# microcontroller3.net
KiCad netlist of a schematic drawn in Altium Designer
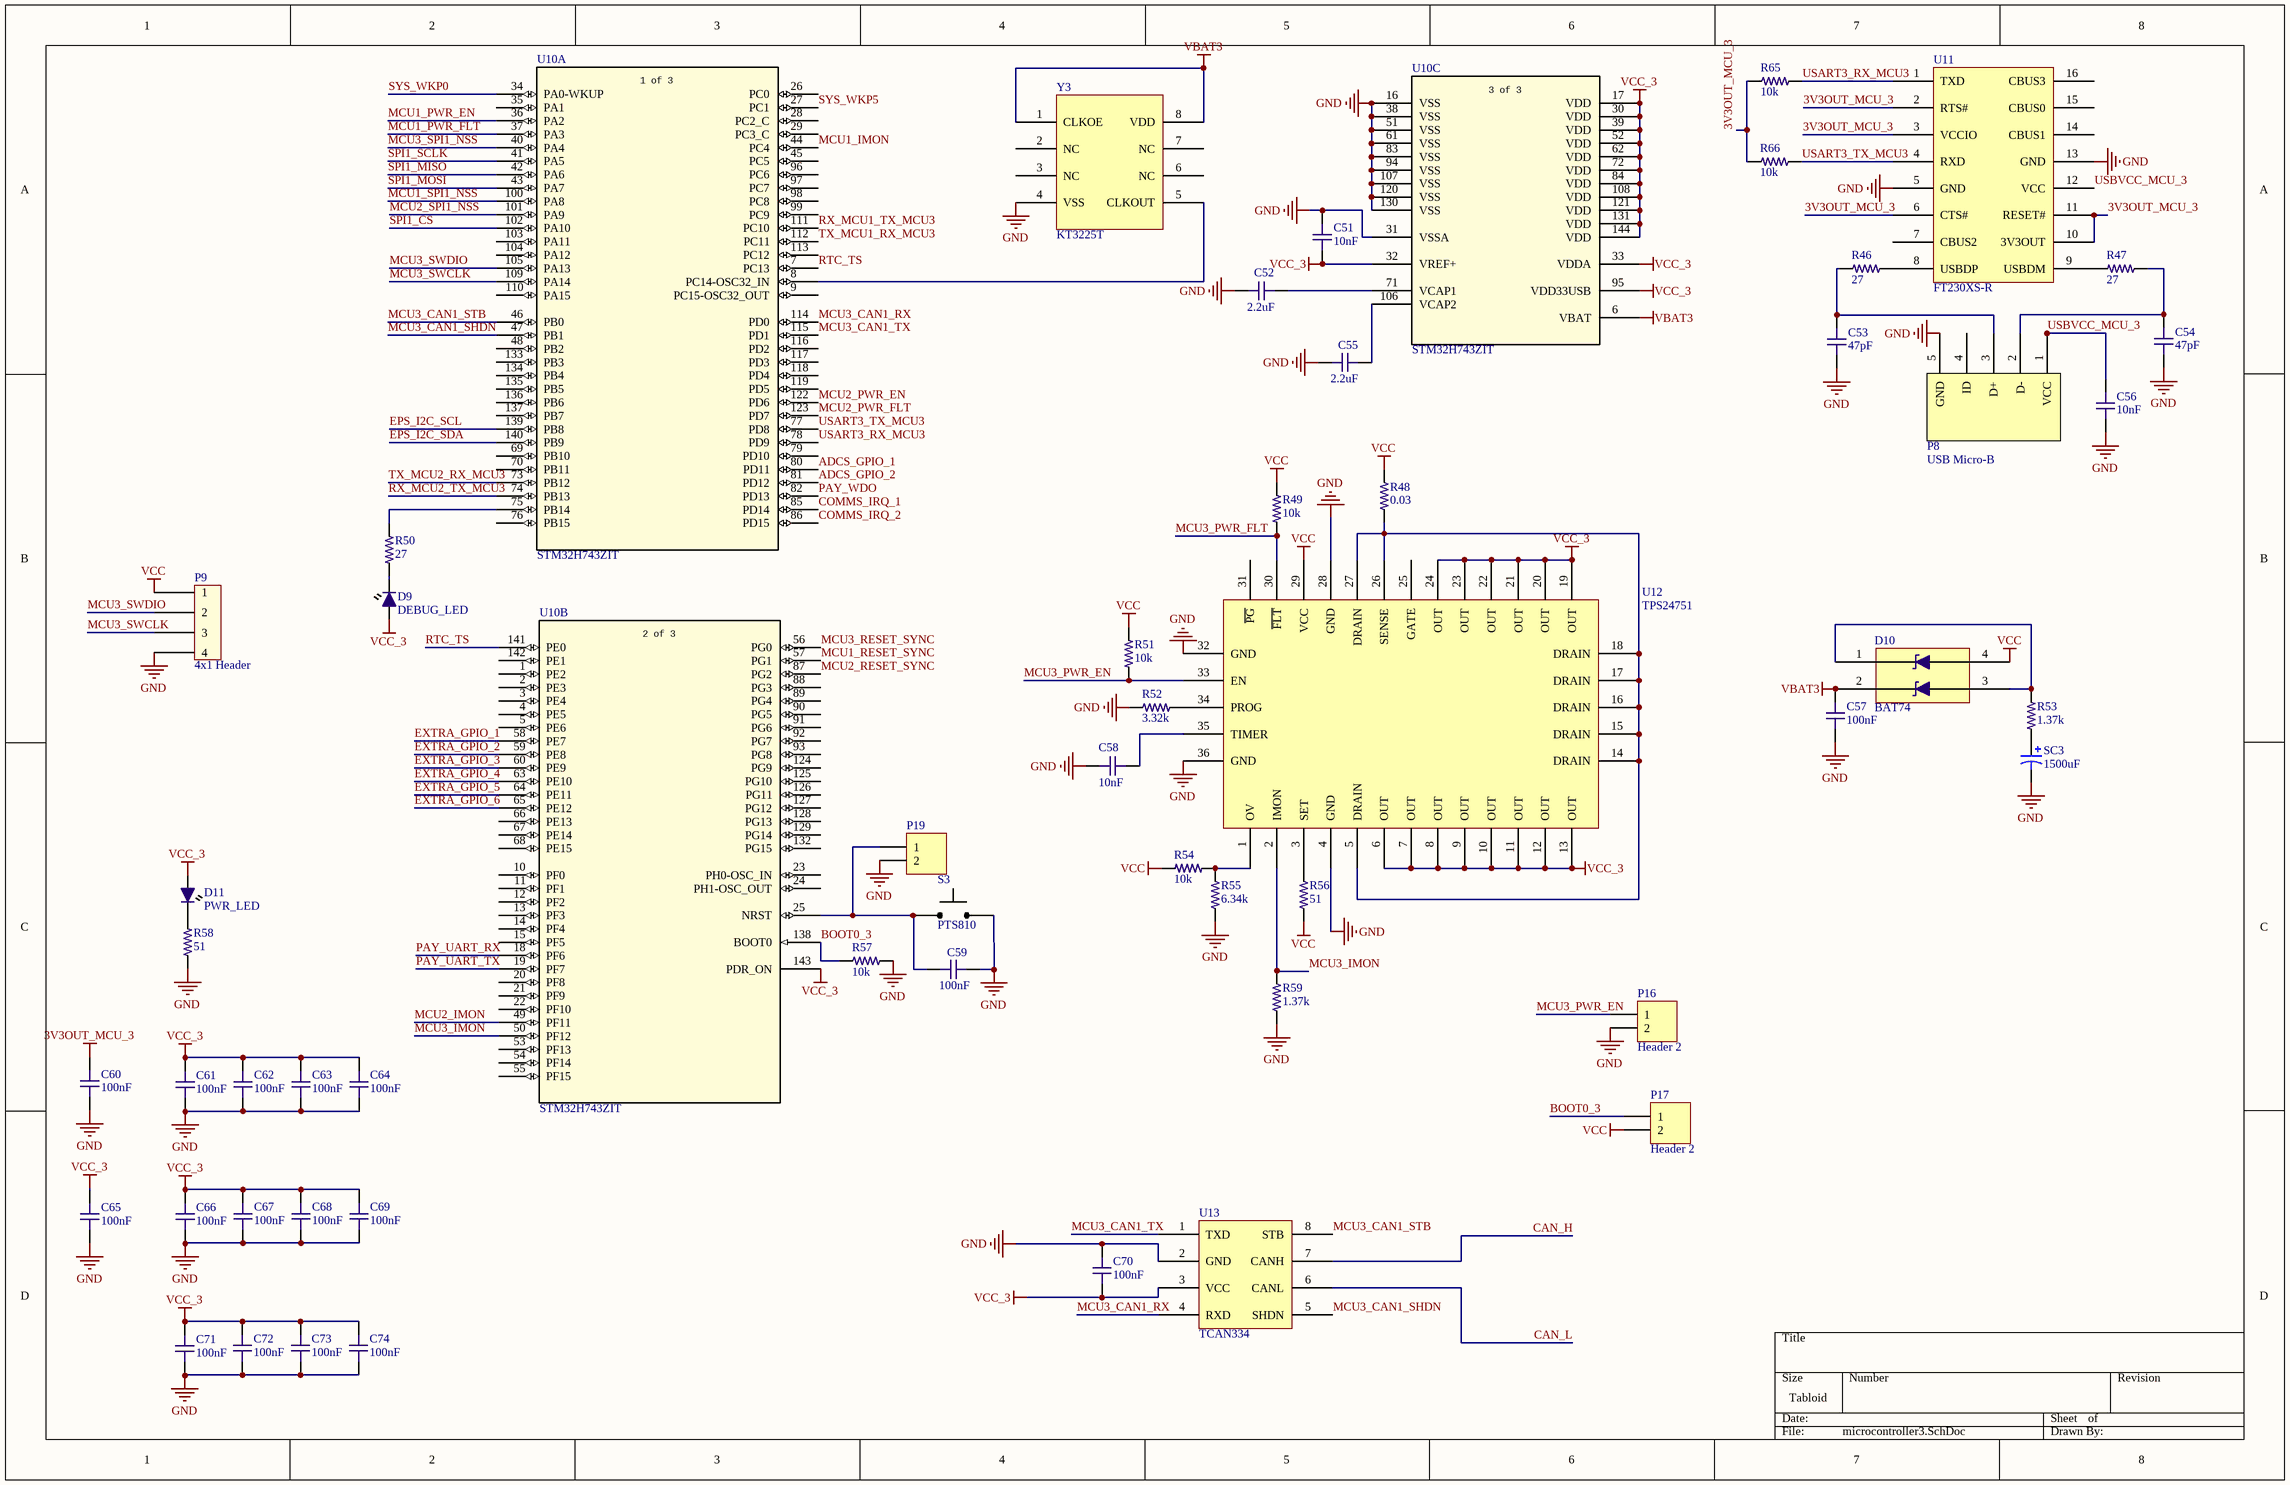
[diagram p0: microcontroller3.SchDoc]

(export (version "E")
  (design (tool "Eeschema 10.0.6"))
  (components
    (comp (ref "C51")
      (value "10nF")
      (footprint "C0603-IPC")
      (description "Chip Capacitor, 0603, ??nF, 10V, X7R")
      (fields (field (name "Comment") "0603 Capacitor Template"))
      (libsource (lib "Capacitors") (part "0603 Capacitor Template"))
    )
    (comp (ref "C52")
      (value "2.2uF")
      (footprint "C0603-IPC")
      (description "Chip Capacitor, 0603, ??nF, 10V, X7R")
      (fields (field (name "Comment") "0603 Capacitor Template"))
      (libsource (lib "Capacitors") (part "0603 Capacitor Template"))
    )
    (comp (ref "C53")
      (value "47pF")
      (footprint "C0603-IPC")
      (description "Chip Capacitor, 0603, ??nF, 10V, X7R")
      (fields (field (name "Comment") "0603 Capacitor Template"))
      (libsource (lib "Capacitors") (part "0603 Capacitor Template"))
    )
    (comp (ref "C54")
      (value "47pF")
      (footprint "C0603-IPC")
      (description "Chip Capacitor, 0603, ??nF, 10V, X7R")
      (fields (field (name "Comment") "0603 Capacitor Template"))
      (libsource (lib "Capacitors") (part "0603 Capacitor Template"))
    )
    (comp (ref "C55")
      (value "2.2uF")
      (footprint "C0603-IPC")
      (description "Chip Capacitor, 0603, ??nF, 10V, X7R")
      (fields (field (name "Comment") "0603 Capacitor Template"))
      (libsource (lib "Capacitors") (part "0603 Capacitor Template"))
    )
    (comp (ref "C56")
      (value "10nF")
      (footprint "C0603-IPC")
      (description "Chip Capacitor, 0603, ??nF, 10V, X7R")
      (fields (field (name "Comment") "0603 Capacitor Template"))
      (libsource (lib "Capacitors") (part "0603 Capacitor Template"))
    )
    (comp (ref "C57")
      (value "100nF")
      (footprint "C0603-IPC")
      (description "Chip Capacitor, 0603, ??nF, 10V, X7R")
      (fields (field (name "Comment") "0603 Capacitor Template"))
      (libsource (lib "Capacitors") (part "0603 Capacitor Template"))
    )
    (comp (ref "C58")
      (value "10nF")
      (footprint "C0603-IPC")
      (description "Chip Capacitor, 0603, ??nF, 10V, X7R")
      (fields (field (name "Comment") "0603 Capacitor Template"))
      (libsource (lib "Capacitors") (part "0603 Capacitor Template"))
    )
    (comp (ref "C59")
      (value "100nF")
      (footprint "C0603-IPC")
      (description "Chip Capacitor, 0603, ??nF, 10V, X7R")
      (fields (field (name "Comment") "0603 Capacitor Template"))
      (libsource (lib "Capacitors") (part "0603 Capacitor Template"))
    )
    (comp (ref "C60")
      (value "100nF")
      (footprint "C0603-IPC")
      (description "Chip Capacitor, 0603, ??nF, 10V, X7R")
      (fields (field (name "Comment") "0603 Capacitor Template"))
      (libsource (lib "Capacitors") (part "0603 Capacitor Template"))
    )
    (comp (ref "C61")
      (value "100nF")
      (footprint "C0603-IPC")
      (description "Chip Capacitor, 0603, ??nF, 10V, X7R")
      (fields (field (name "Comment") "0603 Capacitor Template"))
      (libsource (lib "Capacitors") (part "0603 Capacitor Template"))
    )
    (comp (ref "C62")
      (value "100nF")
      (footprint "C0603-IPC")
      (description "Chip Capacitor, 0603, ??nF, 10V, X7R")
      (fields (field (name "Comment") "0603 Capacitor Template"))
      (libsource (lib "Capacitors") (part "0603 Capacitor Template"))
    )
    (comp (ref "C63")
      (value "100nF")
      (footprint "C0603-IPC")
      (description "Chip Capacitor, 0603, ??nF, 10V, X7R")
      (fields (field (name "Comment") "0603 Capacitor Template"))
      (libsource (lib "Capacitors") (part "0603 Capacitor Template"))
    )
    (comp (ref "C64")
      (value "100nF")
      (footprint "C0603-IPC")
      (description "Chip Capacitor, 0603, ??nF, 10V, X7R")
      (fields (field (name "Comment") "0603 Capacitor Template"))
      (libsource (lib "Capacitors") (part "0603 Capacitor Template"))
    )
    (comp (ref "C65")
      (value "100nF")
      (footprint "C0603-IPC")
      (description "Chip Capacitor, 0603, ??nF, 10V, X7R")
      (fields (field (name "Comment") "0603 Capacitor Template"))
      (libsource (lib "Capacitors") (part "0603 Capacitor Template"))
    )
    (comp (ref "C66")
      (value "100nF")
      (footprint "C0603-IPC")
      (description "Chip Capacitor, 0603, ??nF, 10V, X7R")
      (fields (field (name "Comment") "0603 Capacitor Template"))
      (libsource (lib "Capacitors") (part "0603 Capacitor Template"))
    )
    (comp (ref "C67")
      (value "100nF")
      (footprint "C0603-IPC")
      (description "Chip Capacitor, 0603, ??nF, 10V, X7R")
      (fields (field (name "Comment") "0603 Capacitor Template"))
      (libsource (lib "Capacitors") (part "0603 Capacitor Template"))
    )
    (comp (ref "C68")
      (value "100nF")
      (footprint "C0603-IPC")
      (description "Chip Capacitor, 0603, ??nF, 10V, X7R")
      (fields (field (name "Comment") "0603 Capacitor Template"))
      (libsource (lib "Capacitors") (part "0603 Capacitor Template"))
    )
    (comp (ref "C69")
      (value "100nF")
      (footprint "C0603-IPC")
      (description "Chip Capacitor, 0603, ??nF, 10V, X7R")
      (fields (field (name "Comment") "0603 Capacitor Template"))
      (libsource (lib "Capacitors") (part "0603 Capacitor Template"))
    )
    (comp (ref "C70")
      (value "100nF")
      (footprint "C0603-IPC")
      (description "Chip Capacitor, 0603, ??nF, 10V, X7R")
      (fields (field (name "Comment") "0603 Capacitor Template"))
      (libsource (lib "Capacitors") (part "0603 Capacitor Template"))
    )
    (comp (ref "C71")
      (value "100nF")
      (footprint "C0603-IPC")
      (description "Chip Capacitor, 0603, ??nF, 10V, X7R")
      (fields (field (name "Comment") "0603 Capacitor Template"))
      (libsource (lib "Capacitors") (part "0603 Capacitor Template"))
    )
    (comp (ref "C72")
      (value "100nF")
      (footprint "C0603-IPC")
      (description "Chip Capacitor, 0603, ??nF, 10V, X7R")
      (fields (field (name "Comment") "0603 Capacitor Template"))
      (libsource (lib "Capacitors") (part "0603 Capacitor Template"))
    )
    (comp (ref "C73")
      (value "100nF")
      (footprint "C0603-IPC")
      (description "Chip Capacitor, 0603, ??nF, 10V, X7R")
      (fields (field (name "Comment") "0603 Capacitor Template"))
      (libsource (lib "Capacitors") (part "0603 Capacitor Template"))
    )
    (comp (ref "C74")
      (value "100nF")
      (footprint "C0603-IPC")
      (description "Chip Capacitor, 0603, ??nF, 10V, X7R")
      (fields (field (name "Comment") "0603 Capacitor Template"))
      (libsource (lib "Capacitors") (part "0603 Capacitor Template"))
    )
    (comp (ref "D9")
      (value "DEBUG_LED")
      (footprint "LED0603-IPC")
      (description "Blue DEBUG_LED")
      (libsource (lib "Diodes") (part "LED 0603 SMD"))
    )
    (comp (ref "D10")
      (value "BAT74")
      (footprint "SOT190P230X110-4N")
      (description "Barrier Schotkky Double Diode")
      (libsource (lib "Diodes") (part "BAT74"))
    )
    (comp (ref "D11")
      (value "PWR_LED")
      (footprint "LED0603-IPC")
      (description "Red PWR_LED")
      (libsource (lib "Diodes") (part "LED 0603 SMD"))
    )
    (comp (ref "P8")
      (value "USB Micro-B")
      (footprint "Micro USB B")
      (description "CONN RCPT USB TYPE B 3A")
      (fields
        (field (name "MANUFACTURER PART NUMBER") "629105150521")
        (field (name "MANUFACTURER") "Wurth Electronics Inc.")
      )
      (libsource (lib "Connectors") (part "USB Micro-B"))
    )
    (comp (ref "P9")
      (value "4x1 Header")
      (footprint "4X1 HEADER")
      (libsource (lib "Connectors") (part "4x1 Header"))
    )
    (comp (ref "P16")
      (value "Header 2")
      (footprint "HDR1X2")
      (description "Header, 2-Pin")
      (fields (field (name "PUBLISHER") "Altium Limited"))
      (libsource (lib "Miscellaneous Connectors") (part "Header 2"))
    )
    (comp (ref "P17")
      (value "Header 2")
      (footprint "HDR1X2")
      (description "Header, 2-Pin")
      (fields (field (name "PUBLISHER") "Altium Limited"))
      (libsource (lib "Miscellaneous Connectors") (part "Header 2"))
    )
    (comp (ref "P19")
      (value "Header 2")
      (footprint "HDR1X2")
      (description "Header, 2-Pin")
      (fields (field (name "PUBLISHER") "Altium Limited"))
      (libsource (lib "Miscellaneous Connectors") (part "Header 2"))
    )
    (comp (ref "R46")
      (value "27")
      (footprint "R0603-IPC")
      (description "Chip Resistor, 0603, ??k ohms, 0.1W")
      (fields (field (name "Comment") "0603 Template"))
      (libsource (lib "Resistors") (part "0603 Template"))
    )
    (comp (ref "R47")
      (value "27")
      (footprint "R0603-IPC")
      (description "Chip Resistor, 0603, ??k ohms, 0.1W")
      (fields (field (name "Comment") "0603 Template"))
      (libsource (lib "Resistors") (part "0603 Template"))
    )
    (comp (ref "R48")
      (value "0.03")
      (footprint "R2512-IPC")
      (description "Chip Resistor, 2515, ??k ohms")
      (fields (field (name "Comment") "2512 Template"))
      (libsource (lib "Resistors") (part "2512 Template"))
    )
    (comp (ref "R49")
      (value "10k")
      (footprint "R0603-IPC")
      (description "Chip Resistor, 0603, ??k ohms, 0.1W")
      (fields (field (name "Comment") "0603 Template"))
      (libsource (lib "Resistors") (part "0603 Template"))
    )
    (comp (ref "R50")
      (value "27")
      (footprint "R0603-IPC")
      (description "Chip Resistor, 0603, ??k ohms, 0.1W")
      (fields (field (name "Comment") "0603 Template"))
      (libsource (lib "Resistors") (part "0603 Template"))
    )
    (comp (ref "R51")
      (value "10k")
      (footprint "R0603-IPC")
      (description "Chip Resistor, 0603, ??k ohms, 0.1W")
      (fields (field (name "Comment") "0603 Template"))
      (libsource (lib "Resistors") (part "0603 Template"))
    )
    (comp (ref "R52")
      (value "3.32k")
      (footprint "R0603-IPC")
      (description "Chip Resistor, 0603, ??k ohms, 0.1W")
      (fields (field (name "Comment") "0603 Template"))
      (libsource (lib "Resistors") (part "0603 Template"))
    )
    (comp (ref "R53")
      (value "1.37k")
      (footprint "R0603-IPC")
      (description "Chip Resistor, 2515, ??k ohms")
      (fields (field (name "Comment") "2512 Template"))
      (libsource (lib "Resistors") (part "2512 Template"))
    )
    (comp (ref "R54")
      (value "10k")
      (footprint "R0603-IPC")
      (description "Chip Resistor, 0603, ??k ohms, 0.1W")
      (fields (field (name "Comment") "0603 Template"))
      (libsource (lib "Resistors") (part "0603 Template"))
    )
    (comp (ref "R55")
      (value "6.34k")
      (footprint "R0603-IPC")
      (description "Chip Resistor, 0603, ??k ohms, 0.1W")
      (fields (field (name "Comment") "0603 Template"))
      (libsource (lib "Resistors") (part "0603 Template"))
    )
    (comp (ref "R56")
      (value "51")
      (footprint "R0603-IPC")
      (description "Chip Resistor, 0603, ??k ohms, 0.1W")
      (fields (field (name "Comment") "0603 Template"))
      (libsource (lib "Resistors") (part "0603 Template"))
    )
    (comp (ref "R57")
      (value "10k")
      (footprint "R0603-IPC")
      (description "Chip Resistor, 0603, ??k ohms, 0.1W")
      (fields (field (name "Comment") "0603 Template"))
      (libsource (lib "Resistors") (part "0603 Template"))
    )
    (comp (ref "R58")
      (value "51")
      (footprint "R0603-IPC")
      (description "Chip Resistor, 0603, ??k ohms, 0.1W")
      (fields (field (name "Comment") "0603 Template"))
      (libsource (lib "Resistors") (part "0603 Template"))
    )
    (comp (ref "R59")
      (value "1.37k")
      (footprint "R0603-IPC")
      (description "Chip Resistor, 0603, ??k ohms, 0.1W")
      (fields (field (name "Comment") "0603 Template"))
      (libsource (lib "Resistors") (part "0603 Template"))
    )
    (comp (ref "R65")
      (value "10k")
      (footprint "R0603-IPC")
      (description "Chip Resistor, 0603, ??k ohms, 0.1W")
      (fields (field (name "Comment") "0603 Template"))
      (libsource (lib "Resistors") (part "0603 Template"))
    )
    (comp (ref "R66")
      (value "10k")
      (footprint "R0603-IPC")
      (description "Chip Resistor, 0603, ??k ohms, 0.1W")
      (fields (field (name "Comment") "0603 Template"))
      (libsource (lib "Resistors") (part "0603 Template"))
    )
    (comp (ref "S3")
      (value "PTS810")
      (footprint "PTS810")
      (description "SWITCH TACTILE 0.05A 16V")
      (libsource (lib "Switches") (part "PTS810"))
    )
    (comp (ref "SC3")
      (value "1500uF")
      (footprint "C7360-IPC")
      (description "Polarized Capacitor (Radial)")
      (fields (field (name "Comment") "Cap Pol1") (field (name "PUBLISHER") "Altium Limited"))
      (libsource (lib "Miscellaneous Devices") (part "Cap Pol1"))
    )
    (comp (ref "U10")
      (value "STM32H743ZIT")
      (footprint "LQFP50P2200X2200X160-144N")
      (description "IC MCU STM32H7")
      (libsource (lib "Integrated Circuits") (part "STM32H743ZIT"))
    )
    (comp (ref "U11")
      (value "FT230XS-R")
      (footprint "SOP64P600X175-16N")
      (description "FTDI USB to UART IC")
      (libsource (lib "Integrated Circuits") (part "FT230XS-R"))
    )
    (comp (ref "U12")
      (value "TPS24751")
      (footprint "VQFN50P700X350X100-36N")
      (description "eFuse Circuit Protector with Current Monitor")
      (libsource (lib "Integrated Circuits") (part "TPS24751"))
    )
    (comp (ref "U13")
      (value "TCAN334")
      (footprint "SOIC127P600X175-8N")
      (description "3V3 CAN Transceiver")
      (libsource (lib "Integrated Circuits") (part "TCAN334"))
    )
    (comp (ref "Y3")
      (value "KT3225T")
      (footprint "KT3225T XTAL")
      (description "Temperate Compensated Crystal Oscillator")
      (libsource (lib "Integrated Circuits") (part "KT3225T"))
    )
  )
  (nets
    (net (code "1") (name "/ADCS_GPIO_1") (class "Default")
      (node (ref "U10") (pin "80") (pinfunction "PD11_80") (pintype "bidirectional"))
    )
    (net (code "2") (name "/ADCS_GPIO_2") (class "Default")
      (node (ref "U10") (pin "81") (pinfunction "PD12_81") (pintype "bidirectional"))
    )
    (net (code "3") (name "/BOOT0_3") (class "Default")
      (node (ref "P17") (pin "1") (pinfunction "1_1") (pintype "passive"))
      (node (ref "R57") (pin "2") (pintype "passive"))
      (node (ref "U10") (pin "138") (pinfunction "BOOT0_138") (pintype "input"))
    )
    (net (code "4") (name "/CAN_H") (class "Default")
      (node (ref "U13") (pin "7") (pinfunction "CANH_7") (pintype "passive"))
    )
    (net (code "5") (name "/CAN_L") (class "Default")
      (node (ref "U13") (pin "6") (pinfunction "CANL_6") (pintype "passive"))
    )
    (net (code "6") (name "/COMMS_IRQ_1") (class "Default")
      (node (ref "U10") (pin "85") (pinfunction "PD14_85") (pintype "bidirectional"))
    )
    (net (code "7") (name "/COMMS_IRQ_2") (class "Default")
      (node (ref "U10") (pin "86") (pinfunction "PD15_86") (pintype "bidirectional"))
    )
    (net (code "8") (name "/EPS_I2C_SCL") (class "Default")
      (node (ref "U10") (pin "139") (pinfunction "PB8_139") (pintype "bidirectional"))
    )
    (net (code "9") (name "/EPS_I2C_SDA") (class "Default")
      (node (ref "U10") (pin "140") (pinfunction "PB9_140") (pintype "bidirectional"))
    )
    (net (code "10") (name "/EXTRA_GPIO_1") (class "Default")
      (node (ref "U10") (pin "58") (pinfunction "PE7_58") (pintype "bidirectional"))
    )
    (net (code "11") (name "/EXTRA_GPIO_2") (class "Default")
      (node (ref "U10") (pin "59") (pinfunction "PE8_59") (pintype "bidirectional"))
    )
    (net (code "12") (name "/EXTRA_GPIO_3") (class "Default")
      (node (ref "U10") (pin "60") (pinfunction "PE9_60") (pintype "bidirectional"))
    )
    (net (code "13") (name "/EXTRA_GPIO_4") (class "Default")
      (node (ref "U10") (pin "63") (pinfunction "PE10_63") (pintype "bidirectional"))
    )
    (net (code "14") (name "/EXTRA_GPIO_5") (class "Default")
      (node (ref "U10") (pin "64") (pinfunction "PE11_64") (pintype "bidirectional"))
    )
    (net (code "15") (name "/EXTRA_GPIO_6") (class "Default")
      (node (ref "U10") (pin "65") (pinfunction "PE12_65") (pintype "bidirectional"))
    )
    (net (code "16") (name "/MCU1_IMON") (class "Default")
      (node (ref "U10") (pin "44") (pinfunction "PC4_44") (pintype "bidirectional"))
    )
    (net (code "17") (name "/MCU1_PWR_EN") (class "Default")
      (node (ref "U10") (pin "36") (pinfunction "PA2_36") (pintype "bidirectional"))
    )
    (net (code "18") (name "/MCU1_PWR_FLT") (class "Default")
      (node (ref "U10") (pin "37") (pinfunction "PA3_37") (pintype "bidirectional"))
    )
    (net (code "19") (name "/MCU1_RESET_SYNC") (class "Default")
      (node (ref "U10") (pin "57") (pinfunction "PG1_57") (pintype "bidirectional"))
    )
    (net (code "20") (name "/MCU1_SPI1_NSS") (class "Default")
      (node (ref "U10") (pin "100") (pinfunction "PA8_100") (pintype "bidirectional"))
    )
    (net (code "21") (name "/MCU2_IMON") (class "Default")
      (node (ref "U10") (pin "49") (pinfunction "PF11_49") (pintype "bidirectional"))
    )
    (net (code "22") (name "/MCU2_PWR_EN") (class "Default")
      (node (ref "U10") (pin "122") (pinfunction "PD6_122") (pintype "bidirectional"))
    )
    (net (code "23") (name "/MCU2_PWR_FLT") (class "Default")
      (node (ref "U10") (pin "123") (pinfunction "PD7_123") (pintype "bidirectional"))
    )
    (net (code "24") (name "/MCU2_RESET_SYNC") (class "Default")
      (node (ref "U10") (pin "87") (pinfunction "PG2_87") (pintype "bidirectional"))
    )
    (net (code "25") (name "/MCU2_SPI1_NSS") (class "Default")
      (node (ref "U10") (pin "101") (pinfunction "PA9_101") (pintype "bidirectional"))
    )
    (net (code "26") (name "/MCU3_CAN1_RX") (class "Default")
      (node (ref "U10") (pin "114") (pinfunction "PD0_114") (pintype "bidirectional"))
      (node (ref "U13") (pin "4") (pinfunction "RXD_4") (pintype "passive"))
    )
    (net (code "27") (name "/MCU3_CAN1_SHDN") (class "Default")
      (node (ref "U10") (pin "47") (pinfunction "PB1_47") (pintype "bidirectional"))
      (node (ref "U13") (pin "5") (pinfunction "SHDN_5") (pintype "passive"))
    )
    (net (code "28") (name "/MCU3_CAN1_STB") (class "Default")
      (node (ref "U10") (pin "46") (pinfunction "PB0_46") (pintype "bidirectional"))
      (node (ref "U13") (pin "8") (pinfunction "STB_8") (pintype "passive"))
    )
    (net (code "29") (name "/MCU3_CAN1_TX") (class "Default")
      (node (ref "U10") (pin "115") (pinfunction "PD1_115") (pintype "bidirectional"))
      (node (ref "U13") (pin "1") (pinfunction "TXD_1") (pintype "passive"))
    )
    (net (code "30") (name "/MCU3_IMON") (class "Default")
      (node (ref "R59") (pin "2") (pintype "passive"))
      (node (ref "U10") (pin "50") (pinfunction "PF12_50") (pintype "bidirectional"))
      (node (ref "U12") (pin "2") (pinfunction "IMON_2") (pintype "passive"))
    )
    (net (code "31") (name "/MCU3_PWR_EN") (class "Default")
      (node (ref "P16") (pin "1") (pinfunction "1_1") (pintype "passive"))
      (node (ref "R51") (pin "1") (pintype "passive"))
      (node (ref "U12") (pin "33") (pinfunction "EN_33") (pintype "passive"))
    )
    (net (code "32") (name "/MCU3_PWR_FLT") (class "Default")
      (node (ref "R49") (pin "1") (pintype "passive"))
      (node (ref "U12") (pin "30") (pinfunction "~{FLT}_30") (pintype "passive"))
    )
    (net (code "33") (name "/MCU3_RESET_SYNC") (class "Default")
      (node (ref "U10") (pin "56") (pinfunction "PG0_56") (pintype "bidirectional"))
    )
    (net (code "34") (name "/MCU3_SPI1_NSS") (class "Default")
      (node (ref "U10") (pin "40") (pinfunction "PA4_40") (pintype "bidirectional"))
    )
    (net (code "35") (name "/MCU3_SWCLK") (class "Default")
      (node (ref "P9") (pin "3") (pinfunction "3_3") (pintype "passive"))
      (node (ref "U10") (pin "109") (pinfunction "PA14_109") (pintype "bidirectional"))
    )
    (net (code "36") (name "/MCU3_SWDIO") (class "Default")
      (node (ref "P9") (pin "2") (pinfunction "2_2") (pintype "passive"))
      (node (ref "U10") (pin "105") (pinfunction "PA13_105") (pintype "bidirectional"))
    )
    (net (code "37") (name "/PAY_UART_RX") (class "Default")
      (node (ref "U10") (pin "18") (pinfunction "PF6_18") (pintype "bidirectional"))
    )
    (net (code "38") (name "/PAY_UART_TX") (class "Default")
      (node (ref "U10") (pin "19") (pinfunction "PF7_19") (pintype "bidirectional"))
    )
    (net (code "39") (name "/PAY_WDO") (class "Default")
      (node (ref "U10") (pin "82") (pinfunction "PD13_82") (pintype "bidirectional"))
    )
    (net (code "40") (name "/RTC_TS") (class "Default")
      (node (ref "U10") (pin "141") (pinfunction "PE0_141") (pintype "bidirectional"))
      (node (ref "U10") (pin "7") (pinfunction "PC13_7") (pintype "bidirectional"))
    )
    (net (code "41") (name "/RX_MCU1_TX_MCU3") (class "Default")
      (node (ref "U10") (pin "111") (pinfunction "PC10_111") (pintype "bidirectional"))
    )
    (net (code "42") (name "/RX_MCU2_TX_MCU3") (class "Default")
      (node (ref "U10") (pin "74") (pinfunction "PB13_74") (pintype "bidirectional"))
    )
    (net (code "43") (name "/SPI1_CS") (class "Default")
      (node (ref "U10") (pin "102") (pinfunction "PA10_102") (pintype "bidirectional"))
    )
    (net (code "44") (name "/SPI1_MISO") (class "Default")
      (node (ref "U10") (pin "42") (pinfunction "PA6_42") (pintype "bidirectional"))
    )
    (net (code "45") (name "/SPI1_MOSI") (class "Default")
      (node (ref "U10") (pin "43") (pinfunction "PA7_43") (pintype "bidirectional"))
    )
    (net (code "46") (name "/SPI1_SCLK") (class "Default")
      (node (ref "U10") (pin "41") (pinfunction "PA5_41") (pintype "bidirectional"))
    )
    (net (code "47") (name "/SYS_WKP0") (class "Default")
      (node (ref "U10") (pin "34") (pinfunction "PA0-WKUP_34") (pintype "bidirectional"))
    )
    (net (code "48") (name "/SYS_WKP5") (class "Default")
      (node (ref "U10") (pin "27") (pinfunction "PC1_27") (pintype "bidirectional"))
    )
    (net (code "49") (name "/TX_MCU1_RX_MCU3") (class "Default")
      (node (ref "U10") (pin "112") (pinfunction "PC11_112") (pintype "bidirectional"))
    )
    (net (code "50") (name "/TX_MCU2_RX_MCU3") (class "Default")
      (node (ref "U10") (pin "73") (pinfunction "PB12_73") (pintype "bidirectional"))
    )
    (net (code "51") (name "/USART3_RX_MCU3") (class "Default")
      (node (ref "R65") (pin "2") (pintype "passive"))
      (node (ref "U10") (pin "78") (pinfunction "PD9_78") (pintype "bidirectional"))
      (node (ref "U11") (pin "1") (pinfunction "TXD_1") (pintype "passive"))
    )
    (net (code "52") (name "/USART3_TX_MCU3") (class "Default")
      (node (ref "R66") (pin "2") (pintype "passive"))
      (node (ref "U10") (pin "77") (pinfunction "PD8_77") (pintype "bidirectional"))
      (node (ref "U11") (pin "4") (pinfunction "RXD_4") (pintype "passive"))
    )
    (net (code "53") (name "/USBVCC_MCU_3") (class "Default")
      (node (ref "C56") (pin "2") (pintype "passive"))
      (node (ref "P8") (pin "1") (pinfunction "VCC_1") (pintype "passive"))
      (node (ref "U11") (pin "12") (pinfunction "VCC_12") (pintype "passive"))
    )
    (net (code "54") (name "3V3OUT_MCU_3") (class "Default")
      (node (ref "C60") (pin "2") (pintype "passive"))
      (node (ref "R65") (pin "1") (pintype "passive"))
      (node (ref "R66") (pin "1") (pintype "passive"))
      (node (ref "U11") (pin "10") (pinfunction "3V3OUT_10") (pintype "passive"))
      (node (ref "U11") (pin "11") (pinfunction "RESET#_11") (pintype "passive"))
      (node (ref "U11") (pin "2") (pinfunction "RTS#_2") (pintype "passive"))
      (node (ref "U11") (pin "3") (pinfunction "VCCIO_3") (pintype "passive"))
      (node (ref "U11") (pin "6") (pinfunction "CTS#_6") (pintype "passive"))
    )
    (net (code "55") (name "GND") (class "Default")
      (node (ref "C51") (pin "2") (pintype "passive"))
      (node (ref "C52") (pin "1") (pintype "passive"))
      (node (ref "C53") (pin "1") (pintype "passive"))
      (node (ref "C54") (pin "1") (pintype "passive"))
      (node (ref "C55") (pin "1") (pintype "passive"))
      (node (ref "C56") (pin "1") (pintype "passive"))
      (node (ref "C57") (pin "1") (pintype "passive"))
      (node (ref "C58") (pin "1") (pintype "passive"))
      (node (ref "C59") (pin "2") (pintype "passive"))
      (node (ref "C60") (pin "1") (pintype "passive"))
      (node (ref "C61") (pin "1") (pintype "passive"))
      (node (ref "C62") (pin "1") (pintype "passive"))
      (node (ref "C63") (pin "1") (pintype "passive"))
      (node (ref "C64") (pin "1") (pintype "passive"))
      (node (ref "C65") (pin "1") (pintype "passive"))
      (node (ref "C66") (pin "1") (pintype "passive"))
      (node (ref "C67") (pin "1") (pintype "passive"))
      (node (ref "C68") (pin "1") (pintype "passive"))
      (node (ref "C69") (pin "1") (pintype "passive"))
      (node (ref "C70") (pin "2") (pintype "passive"))
      (node (ref "C71") (pin "1") (pintype "passive"))
      (node (ref "C72") (pin "1") (pintype "passive"))
      (node (ref "C73") (pin "1") (pintype "passive"))
      (node (ref "C74") (pin "1") (pintype "passive"))
      (node (ref "P16") (pin "2") (pinfunction "2_2") (pintype "passive"))
      (node (ref "P19") (pin "2") (pinfunction "2_2") (pintype "passive"))
      (node (ref "P8") (pin "5") (pinfunction "GND_5") (pintype "passive"))
      (node (ref "P9") (pin "4") (pinfunction "4_4") (pintype "passive"))
      (node (ref "R52") (pin "1") (pintype "passive"))
      (node (ref "R55") (pin "1") (pintype "passive"))
      (node (ref "R57") (pin "1") (pintype "passive"))
      (node (ref "R58") (pin "2") (pintype "passive"))
      (node (ref "R59") (pin "1") (pintype "passive"))
      (node (ref "S3") (pin "2") (pinfunction "2_2") (pintype "passive"))
      (node (ref "SC3") (pin "2") (pinfunction "2_2") (pintype "passive"))
      (node (ref "U10") (pin "107") (pinfunction "VSS_107") (pintype "power_in"))
      (node (ref "U10") (pin "120") (pinfunction "VSS_120") (pintype "power_in"))
      (node (ref "U10") (pin "130") (pinfunction "VSS_130") (pintype "power_in"))
      (node (ref "U10") (pin "16") (pinfunction "VSS_16") (pintype "power_in"))
      (node (ref "U10") (pin "31") (pinfunction "VSSA_31") (pintype "power_in"))
      (node (ref "U10") (pin "38") (pinfunction "VSS_38") (pintype "power_in"))
      (node (ref "U10") (pin "51") (pinfunction "VSS_51") (pintype "power_in"))
      (node (ref "U10") (pin "61") (pinfunction "VSS_61") (pintype "power_in"))
      (node (ref "U10") (pin "83") (pinfunction "VSS_83") (pintype "power_in"))
      (node (ref "U10") (pin "94") (pinfunction "VSS_94") (pintype "power_in"))
      (node (ref "U11") (pin "13") (pinfunction "GND_13") (pintype "passive"))
      (node (ref "U11") (pin "5") (pinfunction "GND_5") (pintype "passive"))
      (node (ref "U12") (pin "28") (pinfunction "GND_28") (pintype "passive"))
      (node (ref "U12") (pin "32") (pinfunction "GND_32") (pintype "passive"))
      (node (ref "U12") (pin "36") (pinfunction "GND_36") (pintype "passive"))
      (node (ref "U12") (pin "4") (pinfunction "GND_4") (pintype "passive"))
      (node (ref "U13") (pin "2") (pinfunction "GND_2") (pintype "passive"))
      (node (ref "Y3") (pin "4") (pinfunction "VSS_4") (pintype "passive"))
    )
    (net (code "56") (name "Net-(D9-PadK)") (class "Default")
      (node (ref "D9") (pin "K") (pintype "passive"))
      (node (ref "R50") (pin "1") (pintype "passive"))
    )
    (net (code "57") (name "Net-(D10-Pad1)") (class "Default")
      (node (ref "D10") (pin "1") (pinfunction "1_1") (pintype "passive"))
      (node (ref "D10") (pin "3") (pinfunction "3_3") (pintype "passive"))
      (node (ref "R53") (pin "2") (pintype "passive"))
    )
    (net (code "58") (name "Net-(D11-PadK)") (class "Default")
      (node (ref "D11") (pin "K") (pintype "passive"))
      (node (ref "R58") (pin "1") (pintype "passive"))
    )
    (net (code "59") (name "Net-(P8-D+)") (class "Default")
      (node (ref "C53") (pin "2") (pintype "passive"))
      (node (ref "P8") (pin "3") (pinfunction "D+_3") (pintype "passive"))
      (node (ref "R46") (pin "1") (pintype "passive"))
    )
    (net (code "60") (name "Net-(P8-D-)") (class "Default")
      (node (ref "C54") (pin "2") (pintype "passive"))
      (node (ref "P8") (pin "2") (pinfunction "D-_2") (pintype "passive"))
      (node (ref "R47") (pin "2") (pintype "passive"))
    )
    (net (code "61") (name "Net-(R53-Pad1)") (class "Default")
      (node (ref "R53") (pin "1") (pintype "passive"))
      (node (ref "SC3") (pin "1") (pinfunction "1_1") (pintype "passive"))
    )
    (net (code "62") (name "Net-(U10A-PB14)") (class "Default")
      (node (ref "R50") (pin "2") (pintype "passive"))
      (node (ref "U10") (pin "75") (pinfunction "PB14_75") (pintype "bidirectional"))
    )
    (net (code "63") (name "Net-(U10A-PC14-OSC32_IN)") (class "Default")
      (node (ref "U10") (pin "8") (pinfunction "PC14-OSC32_IN_8") (pintype "bidirectional"))
      (node (ref "Y3") (pin "5") (pinfunction "CLKOUT_5") (pintype "passive"))
    )
    (net (code "64") (name "Net-(U10B-NRST)") (class "Default")
      (node (ref "C59") (pin "1") (pintype "passive"))
      (node (ref "P19") (pin "1") (pinfunction "1_1") (pintype "passive"))
      (node (ref "S3") (pin "1") (pinfunction "1_1") (pintype "passive"))
      (node (ref "U10") (pin "25") (pinfunction "NRST_25") (pintype "bidirectional"))
    )
    (net (code "65") (name "Net-(U10C-VCAP1)") (class "Default")
      (node (ref "C52") (pin "2") (pintype "passive"))
      (node (ref "U10") (pin "71") (pinfunction "VCAP1_71") (pintype "power_in"))
    )
    (net (code "66") (name "Net-(U10C-VCAP2)") (class "Default")
      (node (ref "C55") (pin "2") (pintype "passive"))
      (node (ref "U10") (pin "106") (pinfunction "VCAP2_106") (pintype "power_in"))
    )
    (net (code "67") (name "Net-(U11-USBDM)") (class "Default")
      (node (ref "R47") (pin "1") (pintype "passive"))
      (node (ref "U11") (pin "9") (pinfunction "USBDM_9") (pintype "passive"))
    )
    (net (code "68") (name "Net-(U11-USBDP)") (class "Default")
      (node (ref "R46") (pin "2") (pintype "passive"))
      (node (ref "U11") (pin "8") (pinfunction "USBDP_8") (pintype "passive"))
    )
    (net (code "69") (name "Net-(U12-OV)") (class "Default")
      (node (ref "R54") (pin "2") (pintype "passive"))
      (node (ref "R55") (pin "2") (pintype "passive"))
      (node (ref "U12") (pin "1") (pinfunction "OV_1") (pintype "passive"))
    )
    (net (code "70") (name "Net-(U12-PROG)") (class "Default")
      (node (ref "R52") (pin "2") (pintype "passive"))
      (node (ref "U12") (pin "34") (pinfunction "PROG_34") (pintype "passive"))
    )
    (net (code "71") (name "Net-(U12-SENSE)") (class "Default")
      (node (ref "R48") (pin "2") (pintype "passive"))
      (node (ref "U12") (pin "14") (pinfunction "DRAIN_14") (pintype "passive"))
      (node (ref "U12") (pin "15") (pinfunction "DRAIN_15") (pintype "passive"))
      (node (ref "U12") (pin "16") (pinfunction "DRAIN_16") (pintype "passive"))
      (node (ref "U12") (pin "17") (pinfunction "DRAIN_17") (pintype "passive"))
      (node (ref "U12") (pin "18") (pinfunction "DRAIN_18") (pintype "passive"))
      (node (ref "U12") (pin "26") (pinfunction "SENSE_26") (pintype "passive"))
      (node (ref "U12") (pin "27") (pinfunction "DRAIN_27") (pintype "passive"))
      (node (ref "U12") (pin "5") (pinfunction "DRAIN_5") (pintype "passive"))
    )
    (net (code "72") (name "Net-(U12-SET)") (class "Default")
      (node (ref "R56") (pin "2") (pintype "passive"))
      (node (ref "U12") (pin "3") (pinfunction "SET_3") (pintype "passive"))
    )
    (net (code "73") (name "Net-(U12-TIMER)") (class "Default")
      (node (ref "C58") (pin "2") (pintype "passive"))
      (node (ref "U12") (pin "35") (pinfunction "TIMER_35") (pintype "passive"))
    )
    (net (code "74") (name "VBAT3") (class "Default")
      (node (ref "C57") (pin "2") (pintype "passive"))
      (node (ref "D10") (pin "2") (pinfunction "2_2") (pintype "passive"))
      (node (ref "U10") (pin "6") (pinfunction "VBAT_6") (pintype "power_in"))
      (node (ref "Y3") (pin "1") (pinfunction "CLKOE_1") (pintype "passive"))
      (node (ref "Y3") (pin "8") (pinfunction "VDD_8") (pintype "passive"))
    )
    (net (code "75") (name "VCC") (class "Default")
      (node (ref "D10") (pin "4") (pinfunction "4_4") (pintype "passive"))
      (node (ref "P17") (pin "2") (pinfunction "2_2") (pintype "passive"))
      (node (ref "P9") (pin "1") (pinfunction "1_1") (pintype "passive"))
      (node (ref "R48") (pin "1") (pintype "passive"))
      (node (ref "R49") (pin "2") (pintype "passive"))
      (node (ref "R51") (pin "2") (pintype "passive"))
      (node (ref "R54") (pin "1") (pintype "passive"))
      (node (ref "R56") (pin "1") (pintype "passive"))
      (node (ref "U12") (pin "29") (pinfunction "VCC_29") (pintype "passive"))
    )
    (net (code "76") (name "VCC_3") (class "Default")
      (node (ref "C51") (pin "1") (pintype "passive"))
      (node (ref "C61") (pin "2") (pintype "passive"))
      (node (ref "C62") (pin "2") (pintype "passive"))
      (node (ref "C63") (pin "2") (pintype "passive"))
      (node (ref "C64") (pin "2") (pintype "passive"))
      (node (ref "C65") (pin "2") (pintype "passive"))
      (node (ref "C66") (pin "2") (pintype "passive"))
      (node (ref "C67") (pin "2") (pintype "passive"))
      (node (ref "C68") (pin "2") (pintype "passive"))
      (node (ref "C69") (pin "2") (pintype "passive"))
      (node (ref "C70") (pin "1") (pintype "passive"))
      (node (ref "C71") (pin "2") (pintype "passive"))
      (node (ref "C72") (pin "2") (pintype "passive"))
      (node (ref "C73") (pin "2") (pintype "passive"))
      (node (ref "C74") (pin "2") (pintype "passive"))
      (node (ref "D11") (pin "A") (pintype "passive"))
      (node (ref "D9") (pin "A") (pintype "passive"))
      (node (ref "U10") (pin "108") (pinfunction "VDD_108") (pintype "power_in"))
      (node (ref "U10") (pin "121") (pinfunction "VDD_121") (pintype "power_in"))
      (node (ref "U10") (pin "131") (pinfunction "VDD_131") (pintype "power_in"))
      (node (ref "U10") (pin "143") (pinfunction "PDR_ON_143") (pintype "passive"))
      (node (ref "U10") (pin "144") (pinfunction "VDD_144") (pintype "power_in"))
      (node (ref "U10") (pin "17") (pinfunction "VDD_17") (pintype "power_in"))
      (node (ref "U10") (pin "30") (pinfunction "VDD_30") (pintype "power_in"))
      (node (ref "U10") (pin "32") (pinfunction "VREF+_32") (pintype "power_in"))
      (node (ref "U10") (pin "33") (pinfunction "VDDA_33") (pintype "power_in"))
      (node (ref "U10") (pin "39") (pinfunction "VDD_39") (pintype "power_in"))
      (node (ref "U10") (pin "52") (pinfunction "VDD_52") (pintype "power_in"))
      (node (ref "U10") (pin "62") (pinfunction "VDD_62") (pintype "power_in"))
      (node (ref "U10") (pin "72") (pinfunction "VDD_72") (pintype "power_in"))
      (node (ref "U10") (pin "84") (pinfunction "VDD_84") (pintype "power_in"))
      (node (ref "U10") (pin "95") (pinfunction "VDD33USB_95") (pintype "power_in"))
      (node (ref "U12") (pin "10") (pinfunction "OUT_10") (pintype "passive"))
      (node (ref "U12") (pin "11") (pinfunction "OUT_11") (pintype "passive"))
      (node (ref "U12") (pin "12") (pinfunction "OUT_12") (pintype "passive"))
      (node (ref "U12") (pin "13") (pinfunction "OUT_13") (pintype "passive"))
      (node (ref "U12") (pin "19") (pinfunction "OUT_19") (pintype "passive"))
      (node (ref "U12") (pin "20") (pinfunction "OUT_20") (pintype "passive"))
      (node (ref "U12") (pin "21") (pinfunction "OUT_21") (pintype "passive"))
      (node (ref "U12") (pin "22") (pinfunction "OUT_22") (pintype "passive"))
      (node (ref "U12") (pin "23") (pinfunction "OUT_23") (pintype "passive"))
      (node (ref "U12") (pin "24") (pinfunction "OUT_24") (pintype "passive"))
      (node (ref "U12") (pin "6") (pinfunction "OUT_6") (pintype "passive"))
      (node (ref "U12") (pin "7") (pinfunction "OUT_7") (pintype "passive"))
      (node (ref "U12") (pin "8") (pinfunction "OUT_8") (pintype "passive"))
      (node (ref "U12") (pin "9") (pinfunction "OUT_9") (pintype "passive"))
      (node (ref "U13") (pin "3") (pinfunction "VCC_3") (pintype "passive"))
    )
    (net (code "77") (name "unconnected-(P8-ID-Pad4)") (class "Default")
      (node (ref "P8") (pin "4") (pinfunction "ID_4") (pintype "passive"))
    )
    (net (code "78") (name "unconnected-(U10A-PA1-Pad35)") (class "Default")
      (node (ref "U10") (pin "35") (pinfunction "PA1_35") (pintype "bidirectional"))
    )
    (net (code "79") (name "unconnected-(U10A-PA11-Pad103)") (class "Default")
      (node (ref "U10") (pin "103") (pinfunction "PA11_103") (pintype "bidirectional"))
    )
    (net (code "80") (name "unconnected-(U10A-PA12-Pad104)") (class "Default")
      (node (ref "U10") (pin "104") (pinfunction "PA12_104") (pintype "bidirectional"))
    )
    (net (code "81") (name "unconnected-(U10A-PA15-Pad110)") (class "Default")
      (node (ref "U10") (pin "110") (pinfunction "PA15_110") (pintype "bidirectional"))
    )
    (net (code "82") (name "unconnected-(U10A-PB2-Pad48)") (class "Default")
      (node (ref "U10") (pin "48") (pinfunction "PB2_48") (pintype "bidirectional"))
    )
    (net (code "83") (name "unconnected-(U10A-PB3-Pad133)") (class "Default")
      (node (ref "U10") (pin "133") (pinfunction "PB3_133") (pintype "bidirectional"))
    )
    (net (code "84") (name "unconnected-(U10A-PB4-Pad134)") (class "Default")
      (node (ref "U10") (pin "134") (pinfunction "PB4_134") (pintype "bidirectional"))
    )
    (net (code "85") (name "unconnected-(U10A-PB5-Pad135)") (class "Default")
      (node (ref "U10") (pin "135") (pinfunction "PB5_135") (pintype "bidirectional"))
    )
    (net (code "86") (name "unconnected-(U10A-PB6-Pad136)") (class "Default")
      (node (ref "U10") (pin "136") (pinfunction "PB6_136") (pintype "bidirectional"))
    )
    (net (code "87") (name "unconnected-(U10A-PB7-Pad137)") (class "Default")
      (node (ref "U10") (pin "137") (pinfunction "PB7_137") (pintype "bidirectional"))
    )
    (net (code "88") (name "unconnected-(U10A-PB10-Pad69)") (class "Default")
      (node (ref "U10") (pin "69") (pinfunction "PB10_69") (pintype "bidirectional"))
    )
    (net (code "89") (name "unconnected-(U10A-PB11-Pad70)") (class "Default")
      (node (ref "U10") (pin "70") (pinfunction "PB11_70") (pintype "bidirectional"))
    )
    (net (code "90") (name "unconnected-(U10A-PB15-Pad76)") (class "Default")
      (node (ref "U10") (pin "76") (pinfunction "PB15_76") (pintype "bidirectional"))
    )
    (net (code "91") (name "unconnected-(U10A-PC0-Pad26)") (class "Default")
      (node (ref "U10") (pin "26") (pinfunction "PC0_26") (pintype "bidirectional"))
    )
    (net (code "92") (name "unconnected-(U10A-PC2_C-Pad28)") (class "Default")
      (node (ref "U10") (pin "28") (pinfunction "PC2_C_28") (pintype "bidirectional"))
    )
    (net (code "93") (name "unconnected-(U10A-PC3_C-Pad29)") (class "Default")
      (node (ref "U10") (pin "29") (pinfunction "PC3_C_29") (pintype "bidirectional"))
    )
    (net (code "94") (name "unconnected-(U10A-PC5-Pad45)") (class "Default")
      (node (ref "U10") (pin "45") (pinfunction "PC5_45") (pintype "bidirectional"))
    )
    (net (code "95") (name "unconnected-(U10A-PC6-Pad96)") (class "Default")
      (node (ref "U10") (pin "96") (pinfunction "PC6_96") (pintype "bidirectional"))
    )
    (net (code "96") (name "unconnected-(U10A-PC7-Pad97)") (class "Default")
      (node (ref "U10") (pin "97") (pinfunction "PC7_97") (pintype "bidirectional"))
    )
    (net (code "97") (name "unconnected-(U10A-PC8-Pad98)") (class "Default")
      (node (ref "U10") (pin "98") (pinfunction "PC8_98") (pintype "bidirectional"))
    )
    (net (code "98") (name "unconnected-(U10A-PC9-Pad99)") (class "Default")
      (node (ref "U10") (pin "99") (pinfunction "PC9_99") (pintype "bidirectional"))
    )
    (net (code "99") (name "unconnected-(U10A-PC12-Pad113)") (class "Default")
      (node (ref "U10") (pin "113") (pinfunction "PC12_113") (pintype "bidirectional"))
    )
    (net (code "100") (name "unconnected-(U10A-PC15-OSC32_OUT-Pad9)") (class "Default")
      (node (ref "U10") (pin "9") (pinfunction "PC15-OSC32_OUT_9") (pintype "bidirectional"))
    )
    (net (code "101") (name "unconnected-(U10A-PD2-Pad116)") (class "Default")
      (node (ref "U10") (pin "116") (pinfunction "PD2_116") (pintype "bidirectional"))
    )
    (net (code "102") (name "unconnected-(U10A-PD3-Pad117)") (class "Default")
      (node (ref "U10") (pin "117") (pinfunction "PD3_117") (pintype "bidirectional"))
    )
    (net (code "103") (name "unconnected-(U10A-PD4-Pad118)") (class "Default")
      (node (ref "U10") (pin "118") (pinfunction "PD4_118") (pintype "bidirectional"))
    )
    (net (code "104") (name "unconnected-(U10A-PD5-Pad119)") (class "Default")
      (node (ref "U10") (pin "119") (pinfunction "PD5_119") (pintype "bidirectional"))
    )
    (net (code "105") (name "unconnected-(U10A-PD10-Pad79)") (class "Default")
      (node (ref "U10") (pin "79") (pinfunction "PD10_79") (pintype "bidirectional"))
    )
    (net (code "106") (name "unconnected-(U10B-PE1-Pad142)") (class "Default")
      (node (ref "U10") (pin "142") (pinfunction "PE1_142") (pintype "bidirectional"))
    )
    (net (code "107") (name "unconnected-(U10B-PE2-Pad1)") (class "Default")
      (node (ref "U10") (pin "1") (pinfunction "PE2_1") (pintype "bidirectional"))
    )
    (net (code "108") (name "unconnected-(U10B-PE3-Pad2)") (class "Default")
      (node (ref "U10") (pin "2") (pinfunction "PE3_2") (pintype "bidirectional"))
    )
    (net (code "109") (name "unconnected-(U10B-PE4-Pad3)") (class "Default")
      (node (ref "U10") (pin "3") (pinfunction "PE4_3") (pintype "bidirectional"))
    )
    (net (code "110") (name "unconnected-(U10B-PE5-Pad4)") (class "Default")
      (node (ref "U10") (pin "4") (pinfunction "PE5_4") (pintype "bidirectional"))
    )
    (net (code "111") (name "unconnected-(U10B-PE6-Pad5)") (class "Default")
      (node (ref "U10") (pin "5") (pinfunction "PE6_5") (pintype "bidirectional"))
    )
    (net (code "112") (name "unconnected-(U10B-PE13-Pad66)") (class "Default")
      (node (ref "U10") (pin "66") (pinfunction "PE13_66") (pintype "bidirectional"))
    )
    (net (code "113") (name "unconnected-(U10B-PE14-Pad67)") (class "Default")
      (node (ref "U10") (pin "67") (pinfunction "PE14_67") (pintype "bidirectional"))
    )
    (net (code "114") (name "unconnected-(U10B-PE15-Pad68)") (class "Default")
      (node (ref "U10") (pin "68") (pinfunction "PE15_68") (pintype "bidirectional"))
    )
    (net (code "115") (name "unconnected-(U10B-PF0-Pad10)") (class "Default")
      (node (ref "U10") (pin "10") (pinfunction "PF0_10") (pintype "bidirectional"))
    )
    (net (code "116") (name "unconnected-(U10B-PF1-Pad11)") (class "Default")
      (node (ref "U10") (pin "11") (pinfunction "PF1_11") (pintype "bidirectional"))
    )
    (net (code "117") (name "unconnected-(U10B-PF2-Pad12)") (class "Default")
      (node (ref "U10") (pin "12") (pinfunction "PF2_12") (pintype "bidirectional"))
    )
    (net (code "118") (name "unconnected-(U10B-PF3-Pad13)") (class "Default")
      (node (ref "U10") (pin "13") (pinfunction "PF3_13") (pintype "bidirectional"))
    )
    (net (code "119") (name "unconnected-(U10B-PF4-Pad14)") (class "Default")
      (node (ref "U10") (pin "14") (pinfunction "PF4_14") (pintype "bidirectional"))
    )
    (net (code "120") (name "unconnected-(U10B-PF5-Pad15)") (class "Default")
      (node (ref "U10") (pin "15") (pinfunction "PF5_15") (pintype "bidirectional"))
    )
    (net (code "121") (name "unconnected-(U10B-PF8-Pad20)") (class "Default")
      (node (ref "U10") (pin "20") (pinfunction "PF8_20") (pintype "bidirectional"))
    )
    (net (code "122") (name "unconnected-(U10B-PF9-Pad21)") (class "Default")
      (node (ref "U10") (pin "21") (pinfunction "PF9_21") (pintype "bidirectional"))
    )
    (net (code "123") (name "unconnected-(U10B-PF10-Pad22)") (class "Default")
      (node (ref "U10") (pin "22") (pinfunction "PF10_22") (pintype "bidirectional"))
    )
    (net (code "124") (name "unconnected-(U10B-PF13-Pad53)") (class "Default")
      (node (ref "U10") (pin "53") (pinfunction "PF13_53") (pintype "bidirectional"))
    )
    (net (code "125") (name "unconnected-(U10B-PF14-Pad54)") (class "Default")
      (node (ref "U10") (pin "54") (pinfunction "PF14_54") (pintype "bidirectional"))
    )
    (net (code "126") (name "unconnected-(U10B-PF15-Pad55)") (class "Default")
      (node (ref "U10") (pin "55") (pinfunction "PF15_55") (pintype "bidirectional"))
    )
    (net (code "127") (name "unconnected-(U10B-PG3-Pad88)") (class "Default")
      (node (ref "U10") (pin "88") (pinfunction "PG3_88") (pintype "bidirectional"))
    )
    (net (code "128") (name "unconnected-(U10B-PG4-Pad89)") (class "Default")
      (node (ref "U10") (pin "89") (pinfunction "PG4_89") (pintype "bidirectional"))
    )
    (net (code "129") (name "unconnected-(U10B-PG5-Pad90)") (class "Default")
      (node (ref "U10") (pin "90") (pinfunction "PG5_90") (pintype "bidirectional"))
    )
    (net (code "130") (name "unconnected-(U10B-PG6-Pad91)") (class "Default")
      (node (ref "U10") (pin "91") (pinfunction "PG6_91") (pintype "bidirectional"))
    )
    (net (code "131") (name "unconnected-(U10B-PG7-Pad92)") (class "Default")
      (node (ref "U10") (pin "92") (pinfunction "PG7_92") (pintype "bidirectional"))
    )
    (net (code "132") (name "unconnected-(U10B-PG8-Pad93)") (class "Default")
      (node (ref "U10") (pin "93") (pinfunction "PG8_93") (pintype "bidirectional"))
    )
    (net (code "133") (name "unconnected-(U10B-PG9-Pad124)") (class "Default")
      (node (ref "U10") (pin "124") (pinfunction "PG9_124") (pintype "bidirectional"))
    )
    (net (code "134") (name "unconnected-(U10B-PG10-Pad125)") (class "Default")
      (node (ref "U10") (pin "125") (pinfunction "PG10_125") (pintype "bidirectional"))
    )
    (net (code "135") (name "unconnected-(U10B-PG11-Pad126)") (class "Default")
      (node (ref "U10") (pin "126") (pinfunction "PG11_126") (pintype "bidirectional"))
    )
    (net (code "136") (name "unconnected-(U10B-PG12-Pad127)") (class "Default")
      (node (ref "U10") (pin "127") (pinfunction "PG12_127") (pintype "bidirectional"))
    )
    (net (code "137") (name "unconnected-(U10B-PG13-Pad128)") (class "Default")
      (node (ref "U10") (pin "128") (pinfunction "PG13_128") (pintype "bidirectional"))
    )
    (net (code "138") (name "unconnected-(U10B-PG14-Pad129)") (class "Default")
      (node (ref "U10") (pin "129") (pinfunction "PG14_129") (pintype "bidirectional"))
    )
    (net (code "139") (name "unconnected-(U10B-PG15-Pad132)") (class "Default")
      (node (ref "U10") (pin "132") (pinfunction "PG15_132") (pintype "bidirectional"))
    )
    (net (code "140") (name "unconnected-(U10B-PH0-OSC_IN-Pad23)") (class "Default")
      (node (ref "U10") (pin "23") (pinfunction "PH0-OSC_IN_23") (pintype "bidirectional"))
    )
    (net (code "141") (name "unconnected-(U10B-PH1-OSC_OUT-Pad24)") (class "Default")
      (node (ref "U10") (pin "24") (pinfunction "PH1-OSC_OUT_24") (pintype "bidirectional"))
    )
    (net (code "142") (name "unconnected-(U11-CBUS0-Pad15)") (class "Default")
      (node (ref "U11") (pin "15") (pinfunction "CBUS0_15") (pintype "passive"))
    )
    (net (code "143") (name "unconnected-(U11-CBUS1-Pad14)") (class "Default")
      (node (ref "U11") (pin "14") (pinfunction "CBUS1_14") (pintype "passive"))
    )
    (net (code "144") (name "unconnected-(U11-CBUS2-Pad7)") (class "Default")
      (node (ref "U11") (pin "7") (pinfunction "CBUS2_7") (pintype "passive"))
    )
    (net (code "145") (name "unconnected-(U11-CBUS3-Pad16)") (class "Default")
      (node (ref "U11") (pin "16") (pinfunction "CBUS3_16") (pintype "passive"))
    )
    (net (code "146") (name "unconnected-(U12-GATE-Pad25)") (class "Default")
      (node (ref "U12") (pin "25") (pinfunction "GATE_25") (pintype "passive"))
    )
    (net (code "147") (name "unconnected-(U12-~{PG}-Pad31)") (class "Default")
      (node (ref "U12") (pin "31") (pinfunction "~{PG}_31") (pintype "passive"))
    )
    (net (code "148") (name "unconnected-(Y3-NC-Pad2)") (class "Default")
      (node (ref "Y3") (pin "2") (pinfunction "NC_2") (pintype "passive"))
    )
    (net (code "149") (name "unconnected-(Y3-NC-Pad3)") (class "Default")
      (node (ref "Y3") (pin "3") (pinfunction "NC_3") (pintype "passive"))
    )
    (net (code "150") (name "unconnected-(Y3-NC-Pad6)") (class "Default")
      (node (ref "Y3") (pin "6") (pinfunction "NC_6") (pintype "passive"))
    )
    (net (code "151") (name "unconnected-(Y3-NC-Pad7)") (class "Default")
      (node (ref "Y3") (pin "7") (pinfunction "NC_7") (pintype "passive"))
    )
  )
)
